# ProPrj_PW113_RF__2025-07-16.net
KiCad netlist of a schematic drawn in EasyEDA Pro
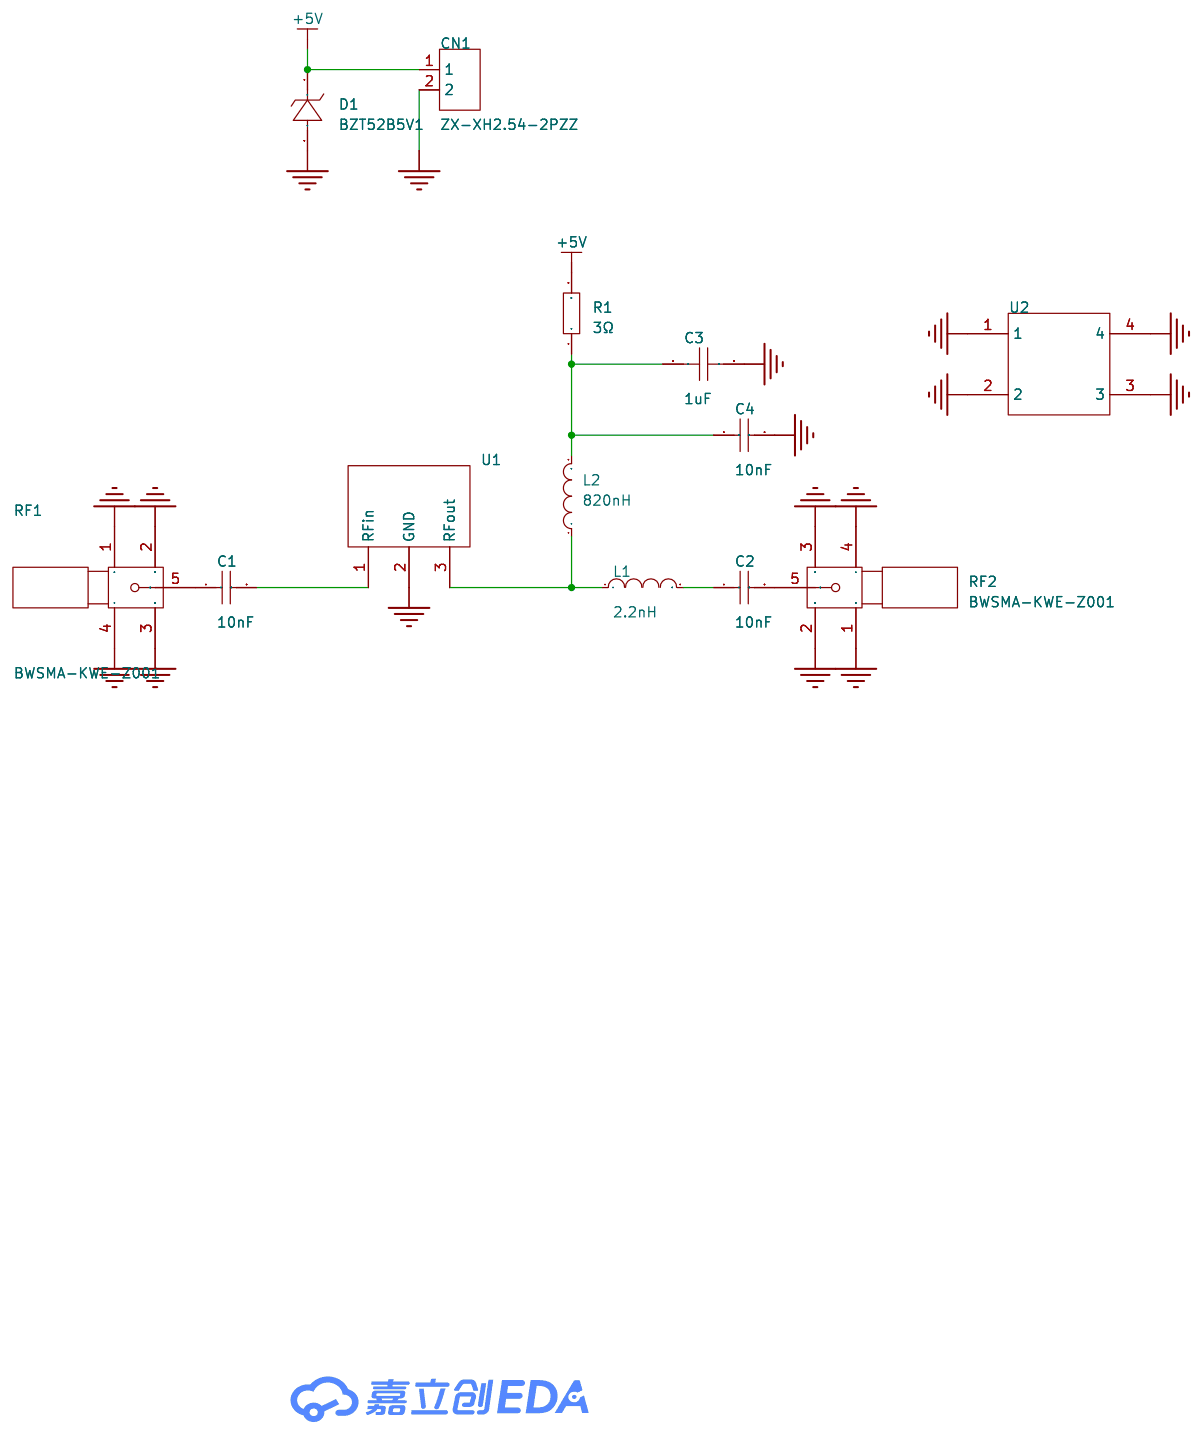
[diagram p0: schematic sheet]

(export (version "E")
  (design (tool "Eeschema 10.0.6"))
  (components
    (comp (ref "C1")
      (value "10nF")
      (footprint "easyedapro:C0603")
      (description "容值:10nF;精度:±10%;额定电压:50V;温度系数:X7R;")
      (fields (field (name "Manufacturer Part") "0603B103K500NT") (field (name "Manufacturer") "FH(风华)"))
      (libsource (lib "easyedapro") (part "0603B103K500NT"))
    )
    (comp (ref "C2")
      (value "10nF")
      (footprint "easyedapro:C0603")
      (description "容值:10nF;精度:±10%;额定电压:50V;温度系数:X7R;")
      (fields (field (name "Manufacturer Part") "0603B103K500NT") (field (name "Manufacturer") "FH(风华)"))
      (libsource (lib "easyedapro") (part "0603B103K500NT"))
    )
    (comp (ref "C3")
      (value "1uF")
      (footprint "easyedapro:C0603")
      (description "容值:1uF;精度:±10%;额定电压:50V;材质(温度系数):X5R;")
      (fields
        (field (name "Manufacturer Part") "CL10A105KB8NNNC")
        (field (name "Manufacturer") "SAMSUNG(三星)")
      )
      (libsource (lib "easyedapro") (part "CL10A105KB8NNNC"))
    )
    (comp (ref "C4")
      (value "10nF")
      (footprint "easyedapro:C0603")
      (description "容值:10nF;精度:±10%;额定电压:50V;温度系数:X7R;")
      (fields (field (name "Manufacturer Part") "0603B103K500NT") (field (name "Manufacturer") "FH(风华)"))
      (libsource (lib "easyedapro") (part "0603B103K500NT"))
    )
    (comp (ref "CN1")
      (value "ZX-XH2.54-2PZZ")
      (footprint "easyedapro:CONN-TH_2P-P2.50_HX25003-2A")
      (fields (field (name "Manufacturer") "Megastar(兆星)"))
      (libsource (lib "easyedapro") (part "ZX-XH2.54-2PZZ"))
    )
    (comp (ref "D1")
      (value "BZT52B5V1")
      (footprint "easyedapro:SOD-123_L2.7-W1.6-LS3.7-RD")
      (description "二极管配置:独立式;稳压值(标称值):5.1V;稳压值(范围):5V~5.2V;耗散功率(Pd):500mW;")
      (fields (field (name "Manufacturer") "宏嘉诚"))
      (libsource (lib "easyedapro") (part "BZT52B5V1_C19077393"))
    )
    (comp (ref "L1")
      (value "2.2nH")
      (footprint "easyedapro:IND-SMD_L1.6-W1.0")
      (description "电感值:2.2nH;精度:±5%;额定电流:700mA;饱和电流(Isat):-;直流电阻(DCR):250mΩ;")
      (fields
        (field (name "Manufacturer Part") "CS0603-2N2J-S")
        (field (name "Manufacturer") "Chilisin(奇力新)")
      )
      (libsource (lib "easyedapro") (part "CS0603-2N2J-S"))
    )
    (comp (ref "L2")
      (value "820nH")
      (footprint "easyedapro:L0603")
      (description "电感值:820nH;精度:±5%;额定电流:70mA;饱和电流(Isat):-;直流电阻(DCR):750mΩ;")
      (fields (field (name "Manufacturer Part") "MLF1608DR82JTD25") (field (name "Manufacturer") "TDK"))
      (libsource (lib "easyedapro") (part "MLF1608DR82JTD25"))
    )
    (comp (ref "R1")
      (value "3Ω")
      (footprint "easyedapro:R0805")
      (description "电阻类型:厚膜电阻;阻值:3Ω;精度:±1%;功率:125mW;工作电压:150V;温度系数:±400ppm/°C;")
      (fields
        (field (name "Manufacturer Part") "0805W8F300KT5E")
        (field (name "Manufacturer") "UNI-ROYAL(厚声)")
      )
      (libsource (lib "easyedapro") (part "0805W8F300KT5E"))
    )
    (comp (ref "RF1")
      (value "BWSMA-KWE-Z001")
      (footprint "easyedapro:SMA-TH_BWSMA-KWE-Z001")
      (fields (field (name "Manufacturer") "BAT WIRELESS(蝙蝠无线)"))
      (libsource (lib "easyedapro") (part "BWSMA-KWE-Z001"))
    )
    (comp (ref "RF2")
      (value "BWSMA-KWE-Z001")
      (footprint "easyedapro:SMA-TH_BWSMA-KWE-Z001")
      (fields (field (name "Manufacturer") "BAT WIRELESS(蝙蝠无线)"))
      (libsource (lib "easyedapro") (part "BWSMA-KWE-Z001"))
    )
    (comp (ref "U1")
      (value "~")
      (footprint "easyedapro:PG-SOT-89-4_L4.5-W2.5-P1.50-LS4.2-TR")
      (description "功放")
      (libsource (lib "easyedapro") (part "PW113"))
    )
    (comp (ref "U2")
      (value "~")
      (footprint "easyedapro:22x17x6")
      (libsource (lib "easyedapro") (part "22x17x6"))
    )
  )
  (nets
    (net (code "1") (name "+5V") (class "Default")
      (node (ref "CN1") (pin "1") (pinfunction "1_1") (pintype "unspecified"))
      (node (ref "D1") (pin "1") (pinfunction "K_1") (pintype "unspecified"))
      (node (ref "R1") (pin "2") (pinfunction "2_2") (pintype "input"))
    )
    (net (code "2") (name "GND") (class "Default")
      (node (ref "C3") (pin "2") (pinfunction "2_2") (pintype "unspecified"))
      (node (ref "C4") (pin "2") (pinfunction "2_2") (pintype "input"))
      (node (ref "CN1") (pin "2") (pinfunction "2_2") (pintype "unspecified"))
      (node (ref "D1") (pin "2") (pinfunction "A_2") (pintype "unspecified"))
      (node (ref "RF1") (pin "1") (pinfunction "1_1") (pintype "unspecified"))
      (node (ref "RF1") (pin "2") (pinfunction "2_2") (pintype "unspecified"))
      (node (ref "RF1") (pin "3") (pinfunction "3_3") (pintype "unspecified"))
      (node (ref "RF1") (pin "4") (pinfunction "4_4") (pintype "unspecified"))
      (node (ref "RF2") (pin "1") (pinfunction "1_1") (pintype "unspecified"))
      (node (ref "RF2") (pin "2") (pinfunction "2_2") (pintype "unspecified"))
      (node (ref "RF2") (pin "3") (pinfunction "3_3") (pintype "unspecified"))
      (node (ref "RF2") (pin "4") (pinfunction "4_4") (pintype "unspecified"))
      (node (ref "U1") (pin "2") (pinfunction "GND_2") (pintype "input"))
      (node (ref "U2") (pin "1") (pinfunction "1_1") (pintype "input"))
      (node (ref "U2") (pin "2") (pinfunction "2_2") (pintype "input"))
      (node (ref "U2") (pin "3") (pinfunction "3_3") (pintype "input"))
      (node (ref "U2") (pin "4") (pinfunction "4_4") (pintype "input"))
    )
    (net (code "3") (name "Net-(C1-Pad1)") (class "Default")
      (node (ref "C1") (pin "1") (pinfunction "1_1") (pintype "input"))
      (node (ref "RF1") (pin "5") (pinfunction "5_5") (pintype "unspecified"))
    )
    (net (code "4") (name "Net-(C2-Pad1)") (class "Default")
      (node (ref "C2") (pin "1") (pinfunction "1_1") (pintype "input"))
      (node (ref "L1") (pin "2") (pinfunction "2_2") (pintype "unspecified"))
    )
    (net (code "5") (name "Net-(C2-Pad2)") (class "Default")
      (node (ref "C2") (pin "2") (pinfunction "2_2") (pintype "input"))
      (node (ref "RF2") (pin "5") (pinfunction "5_5") (pintype "unspecified"))
    )
    (net (code "6") (name "Net-(C3-Pad1)") (class "Default")
      (node (ref "C3") (pin "1") (pinfunction "1_1") (pintype "unspecified"))
      (node (ref "C4") (pin "1") (pinfunction "1_1") (pintype "input"))
      (node (ref "L2") (pin "2") (pinfunction "2_2") (pintype "unspecified"))
      (node (ref "R1") (pin "1") (pinfunction "1_1") (pintype "input"))
    )
    (net (code "7") (name "Net-(U1-RFin)") (class "Default")
      (node (ref "C1") (pin "2") (pinfunction "2_2") (pintype "input"))
      (node (ref "U1") (pin "1") (pinfunction "RFin_1") (pintype "input"))
    )
    (net (code "8") (name "Net-(U1-RFout)") (class "Default")
      (node (ref "L1") (pin "1") (pinfunction "1_1") (pintype "unspecified"))
      (node (ref "L2") (pin "1") (pinfunction "1_1") (pintype "unspecified"))
      (node (ref "U1") (pin "3") (pinfunction "RFout_3") (pintype "input"))
    )
  )
)
